# bugs.net
KiCad netlist of a schematic drawn in EAGLE
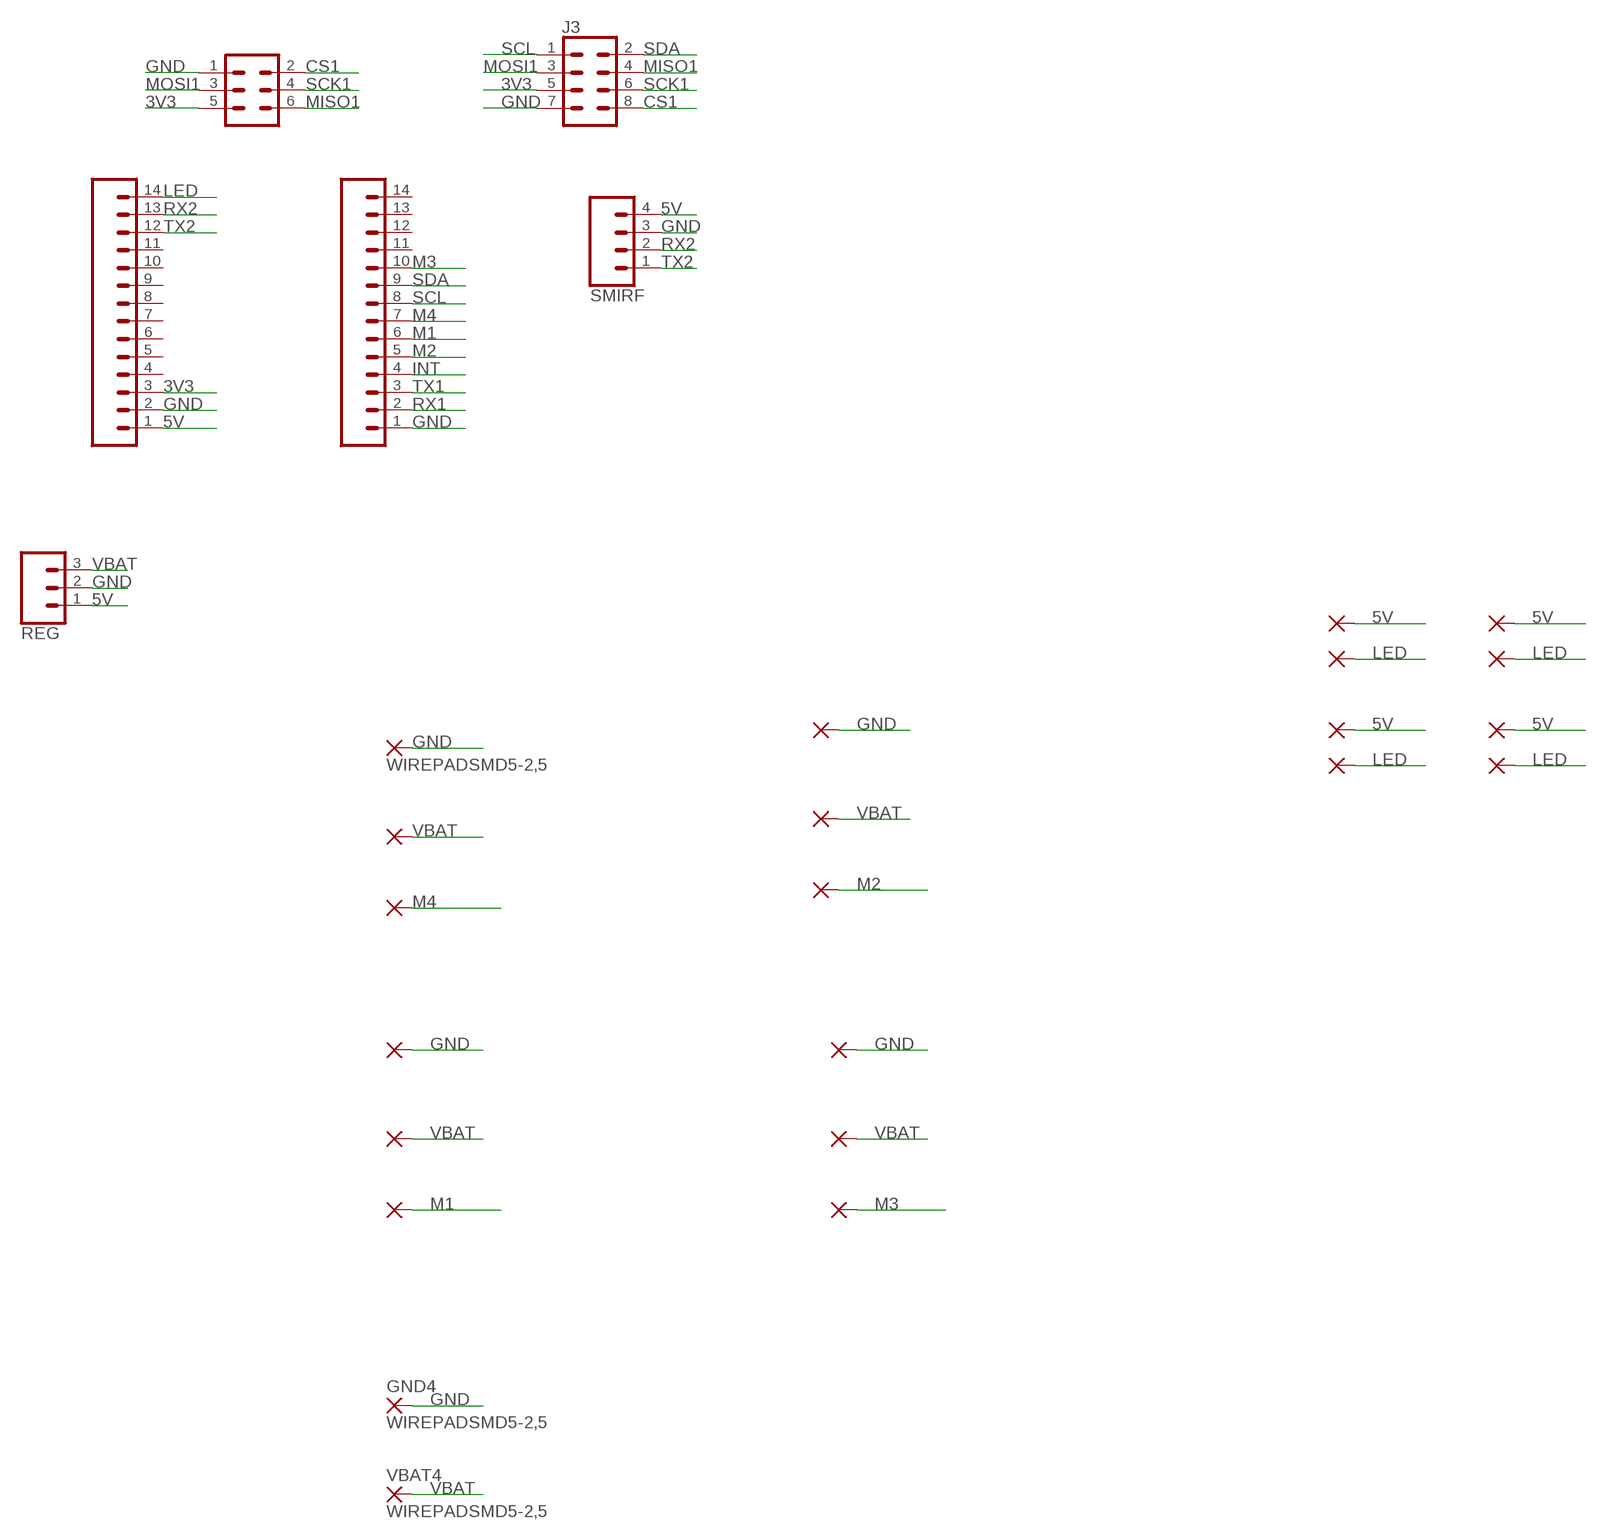
[diagram p0: schematic, sheet 1]

(export (version "E")
  (design (tool "Eeschema 10.0.6"))
  (components
    (comp (ref "GND")
      (value "WIREPADSMD5-2,5")
      (footprint "eagle-import:5-2,5")
      (libsource (lib "eagle-import") (part "WIREPADSMD5-2,5"))
    )
    (comp (ref "GND1")
      (value "WIREPADSMD5-2,5")
      (footprint "eagle-import:5-2,5")
      (libsource (lib "eagle-import") (part "WIREPADSMD5-2,5"))
    )
    (comp (ref "GND2")
      (value "WIREPADSMD5-2,5")
      (footprint "eagle-import:5-2,5")
      (libsource (lib "eagle-import") (part "WIREPADSMD5-2,5"))
    )
    (comp (ref "GND3")
      (value "WIREPADSMD5-2,5")
      (footprint "eagle-import:5-2,5")
      (libsource (lib "eagle-import") (part "WIREPADSMD5-2,5"))
    )
    (comp (ref "GND4")
      (value "WIREPADSMD5-2,5")
      (footprint "eagle-import:5-2,5")
      (libsource (lib "eagle-import") (part "WIREPADSMD5-2,5"))
    )
    (comp (ref "J1")
      (value "CONN_03X2NO_SILK")
      (footprint "eagle-import:2X3-NS")
      (libsource (lib "eagle-import") (part "CONN_03X2NO_SILK"))
    )
    (comp (ref "J3")
      (value "CONN_04X2")
      (footprint "eagle-import:2X4")
      (libsource (lib "eagle-import") (part "CONN_04X2"))
    )
    (comp (ref "J6")
      (value "CONN_14NO_SILK")
      (footprint "eagle-import:1X14_NO_SILK")
      (libsource (lib "eagle-import") (part "CONN_14NO_SILK"))
    )
    (comp (ref "J7")
      (value "CONN_14NO_SILK")
      (footprint "eagle-import:1X14_NO_SILK")
      (libsource (lib "eagle-import") (part "CONN_14NO_SILK"))
    )
    (comp (ref "M1")
      (value "WIREPADSMD5-2,5")
      (footprint "eagle-import:5-2,5")
      (libsource (lib "eagle-import") (part "WIREPADSMD5-2,5"))
    )
    (comp (ref "M2")
      (value "WIREPADSMD5-2,5")
      (footprint "eagle-import:5-2,5")
      (libsource (lib "eagle-import") (part "WIREPADSMD5-2,5"))
    )
    (comp (ref "M3")
      (value "WIREPADSMD5-2,5")
      (footprint "eagle-import:5-2,5")
      (libsource (lib "eagle-import") (part "WIREPADSMD5-2,5"))
    )
    (comp (ref "M4")
      (value "WIREPADSMD5-2,5")
      (footprint "eagle-import:5-2,5")
      (libsource (lib "eagle-import") (part "WIREPADSMD5-2,5"))
    )
    (comp (ref "PAD1")
      (value "SMD2")
      (footprint "eagle-import:SMD1,27-2,54")
      (libsource (lib "eagle-import") (part "SMD2"))
    )
    (comp (ref "PAD2")
      (value "SMD2")
      (footprint "eagle-import:SMD1,27-2,54")
      (libsource (lib "eagle-import") (part "SMD2"))
    )
    (comp (ref "PAD3")
      (value "SMD2")
      (footprint "eagle-import:SMD1,27-2,54")
      (libsource (lib "eagle-import") (part "SMD2"))
    )
    (comp (ref "PAD4")
      (value "SMD2")
      (footprint "eagle-import:SMD1,27-2,54")
      (libsource (lib "eagle-import") (part "SMD2"))
    )
    (comp (ref "PAD5")
      (value "SMD2")
      (footprint "eagle-import:SMD1,27-2,54")
      (libsource (lib "eagle-import") (part "SMD2"))
    )
    (comp (ref "PAD6")
      (value "SMD2")
      (footprint "eagle-import:SMD1,27-2,54")
      (libsource (lib "eagle-import") (part "SMD2"))
    )
    (comp (ref "PAD7")
      (value "SMD2")
      (footprint "eagle-import:SMD1,27-2,54")
      (libsource (lib "eagle-import") (part "SMD2"))
    )
    (comp (ref "PAD8")
      (value "SMD2")
      (footprint "eagle-import:SMD1,27-2,54")
      (libsource (lib "eagle-import") (part "SMD2"))
    )
    (comp (ref "REG")
      (value "REG")
      (footprint "eagle-import:1X03_NO_SILK")
      (libsource (lib "eagle-import") (part "CONN_031X03_NO_SILK"))
    )
    (comp (ref "SMIRF")
      (value "SMIRF")
      (footprint "eagle-import:1X04_NO_SILK")
      (libsource (lib "eagle-import") (part "CONN_041X04_NO_SILK"))
    )
    (comp (ref "VBAT")
      (value "WIREPADSMD5-2,5")
      (footprint "eagle-import:5-2,5")
      (libsource (lib "eagle-import") (part "WIREPADSMD5-2,5"))
    )
    (comp (ref "VBAT1")
      (value "WIREPADSMD5-2,5")
      (footprint "eagle-import:5-2,5")
      (libsource (lib "eagle-import") (part "WIREPADSMD5-2,5"))
    )
    (comp (ref "VBAT2")
      (value "WIREPADSMD5-2,5")
      (footprint "eagle-import:5-2,5")
      (libsource (lib "eagle-import") (part "WIREPADSMD5-2,5"))
    )
    (comp (ref "VBAT3")
      (value "WIREPADSMD5-2,5")
      (footprint "eagle-import:5-2,5")
      (libsource (lib "eagle-import") (part "WIREPADSMD5-2,5"))
    )
    (comp (ref "VBAT4")
      (value "WIREPADSMD5-2,5")
      (footprint "eagle-import:5-2,5")
      (libsource (lib "eagle-import") (part "WIREPADSMD5-2,5"))
    )
  )
  (nets
    (net (code "1") (name "/3V3") (class "Default")
      (node (ref "J1") (pin "5") (pinfunction "5_5") (pintype "bidirectional"))
      (node (ref "J3") (pin "5") (pinfunction "5_5") (pintype "passive"))
      (node (ref "J6") (pin "3") (pinfunction "3_3") (pintype "passive"))
    )
    (net (code "2") (name "/5V") (class "Default")
      (node (ref "J6") (pin "1") (pinfunction "1_1") (pintype "passive"))
      (node (ref "PAD1") (pin "1") (pinfunction "P_1") (pintype "passive"))
      (node (ref "PAD3") (pin "1") (pinfunction "P_1") (pintype "passive"))
      (node (ref "PAD5") (pin "1") (pinfunction "P_1") (pintype "passive"))
      (node (ref "PAD7") (pin "1") (pinfunction "P_1") (pintype "passive"))
      (node (ref "REG") (pin "1") (pinfunction "1_1") (pintype "passive"))
      (node (ref "SMIRF") (pin "4") (pinfunction "4_4") (pintype "passive"))
    )
    (net (code "3") (name "/CS1") (class "Default")
      (node (ref "J1") (pin "2") (pinfunction "2_2") (pintype "bidirectional"))
      (node (ref "J3") (pin "8") (pinfunction "8_8") (pintype "passive"))
    )
    (net (code "4") (name "/GND") (class "Default")
      (node (ref "GND") (pin "1") (pinfunction "P_1") (pintype "passive"))
      (node (ref "GND1") (pin "1") (pinfunction "P_1") (pintype "passive"))
      (node (ref "GND2") (pin "1") (pinfunction "P_1") (pintype "passive"))
      (node (ref "GND3") (pin "1") (pinfunction "P_1") (pintype "passive"))
      (node (ref "GND4") (pin "1") (pinfunction "P_1") (pintype "passive"))
      (node (ref "J1") (pin "1") (pinfunction "1_1") (pintype "bidirectional"))
      (node (ref "J3") (pin "7") (pinfunction "7_7") (pintype "passive"))
      (node (ref "J6") (pin "2") (pinfunction "2_2") (pintype "passive"))
      (node (ref "J7") (pin "1") (pinfunction "1_1") (pintype "passive"))
      (node (ref "REG") (pin "2") (pinfunction "2_2") (pintype "passive"))
      (node (ref "SMIRF") (pin "3") (pinfunction "3_3") (pintype "passive"))
    )
    (net (code "5") (name "/INT") (class "Default")
      (node (ref "J7") (pin "4") (pinfunction "4_4") (pintype "passive"))
    )
    (net (code "6") (name "/LED") (class "Default")
      (node (ref "J6") (pin "14") (pinfunction "14_14") (pintype "passive"))
      (node (ref "PAD2") (pin "1") (pinfunction "P_1") (pintype "passive"))
      (node (ref "PAD4") (pin "1") (pinfunction "P_1") (pintype "passive"))
      (node (ref "PAD6") (pin "1") (pinfunction "P_1") (pintype "passive"))
      (node (ref "PAD8") (pin "1") (pinfunction "P_1") (pintype "passive"))
    )
    (net (code "7") (name "/M1") (class "Default")
      (node (ref "J7") (pin "6") (pinfunction "6_6") (pintype "passive"))
      (node (ref "M1") (pin "1") (pinfunction "P_1") (pintype "passive"))
    )
    (net (code "8") (name "/M2") (class "Default")
      (node (ref "J7") (pin "5") (pinfunction "5_5") (pintype "passive"))
      (node (ref "M2") (pin "1") (pinfunction "P_1") (pintype "passive"))
    )
    (net (code "9") (name "/M3") (class "Default")
      (node (ref "J7") (pin "10") (pinfunction "10_10") (pintype "passive"))
      (node (ref "M3") (pin "1") (pinfunction "P_1") (pintype "passive"))
    )
    (net (code "10") (name "/M4") (class "Default")
      (node (ref "J7") (pin "7") (pinfunction "7_7") (pintype "passive"))
      (node (ref "M4") (pin "1") (pinfunction "P_1") (pintype "passive"))
    )
    (net (code "11") (name "/MISO1") (class "Default")
      (node (ref "J1") (pin "6") (pinfunction "6_6") (pintype "bidirectional"))
      (node (ref "J3") (pin "4") (pinfunction "4_4") (pintype "passive"))
    )
    (net (code "12") (name "/MOSI1") (class "Default")
      (node (ref "J1") (pin "3") (pinfunction "3_3") (pintype "bidirectional"))
      (node (ref "J3") (pin "3") (pinfunction "3_3") (pintype "passive"))
    )
    (net (code "13") (name "/RX1") (class "Default")
      (node (ref "J7") (pin "2") (pinfunction "2_2") (pintype "passive"))
    )
    (net (code "14") (name "/RX2") (class "Default")
      (node (ref "J6") (pin "13") (pinfunction "13_13") (pintype "passive"))
      (node (ref "SMIRF") (pin "2") (pinfunction "2_2") (pintype "passive"))
    )
    (net (code "15") (name "/SCK1") (class "Default")
      (node (ref "J1") (pin "4") (pinfunction "4_4") (pintype "bidirectional"))
      (node (ref "J3") (pin "6") (pinfunction "6_6") (pintype "passive"))
    )
    (net (code "16") (name "/SCL") (class "Default")
      (node (ref "J3") (pin "1") (pinfunction "1_1") (pintype "passive"))
      (node (ref "J7") (pin "8") (pinfunction "8_8") (pintype "passive"))
    )
    (net (code "17") (name "/SDA") (class "Default")
      (node (ref "J3") (pin "2") (pinfunction "2_2") (pintype "passive"))
      (node (ref "J7") (pin "9") (pinfunction "9_9") (pintype "passive"))
    )
    (net (code "18") (name "/TX1") (class "Default")
      (node (ref "J7") (pin "3") (pinfunction "3_3") (pintype "passive"))
    )
    (net (code "19") (name "/TX2") (class "Default")
      (node (ref "J6") (pin "12") (pinfunction "12_12") (pintype "passive"))
      (node (ref "SMIRF") (pin "1") (pinfunction "1_1") (pintype "passive"))
    )
    (net (code "20") (name "/VBAT") (class "Default")
      (node (ref "REG") (pin "3") (pinfunction "3_3") (pintype "passive"))
      (node (ref "VBAT") (pin "1") (pinfunction "P_1") (pintype "passive"))
      (node (ref "VBAT1") (pin "1") (pinfunction "P_1") (pintype "passive"))
      (node (ref "VBAT2") (pin "1") (pinfunction "P_1") (pintype "passive"))
      (node (ref "VBAT3") (pin "1") (pinfunction "P_1") (pintype "passive"))
      (node (ref "VBAT4") (pin "1") (pinfunction "P_1") (pintype "passive"))
    )
    (net (code "21") (name "unconnected-(J6-Pad4)") (class "Default")
      (node (ref "J6") (pin "4") (pinfunction "4_4") (pintype "passive"))
    )
    (net (code "22") (name "unconnected-(J6-Pad5)") (class "Default")
      (node (ref "J6") (pin "5") (pinfunction "5_5") (pintype "passive"))
    )
    (net (code "23") (name "unconnected-(J6-Pad6)") (class "Default")
      (node (ref "J6") (pin "6") (pinfunction "6_6") (pintype "passive"))
    )
    (net (code "24") (name "unconnected-(J6-Pad7)") (class "Default")
      (node (ref "J6") (pin "7") (pinfunction "7_7") (pintype "passive"))
    )
    (net (code "25") (name "unconnected-(J6-Pad8)") (class "Default")
      (node (ref "J6") (pin "8") (pinfunction "8_8") (pintype "passive"))
    )
    (net (code "26") (name "unconnected-(J6-Pad9)") (class "Default")
      (node (ref "J6") (pin "9") (pinfunction "9_9") (pintype "passive"))
    )
    (net (code "27") (name "unconnected-(J6-Pad10)") (class "Default")
      (node (ref "J6") (pin "10") (pinfunction "10_10") (pintype "passive"))
    )
    (net (code "28") (name "unconnected-(J6-Pad11)") (class "Default")
      (node (ref "J6") (pin "11") (pinfunction "11_11") (pintype "passive"))
    )
    (net (code "29") (name "unconnected-(J7-Pad11)") (class "Default")
      (node (ref "J7") (pin "11") (pinfunction "11_11") (pintype "passive"))
    )
    (net (code "30") (name "unconnected-(J7-Pad12)") (class "Default")
      (node (ref "J7") (pin "12") (pinfunction "12_12") (pintype "passive"))
    )
    (net (code "31") (name "unconnected-(J7-Pad13)") (class "Default")
      (node (ref "J7") (pin "13") (pinfunction "13_13") (pintype "passive"))
    )
    (net (code "32") (name "unconnected-(J7-Pad14)") (class "Default")
      (node (ref "J7") (pin "14") (pinfunction "14_14") (pintype "passive"))
    )
  )
)
